# Dual_Supply_AC-DC.net
KiCad netlist of a schematic drawn in EAGLE
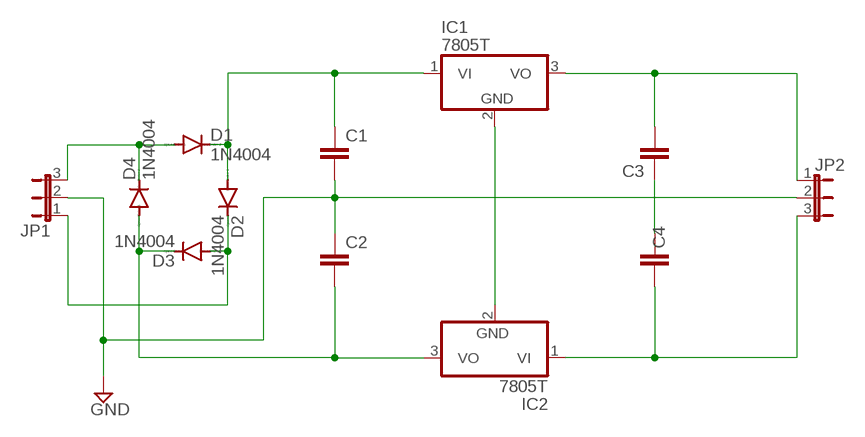
[diagram p0: schematic, sheet 1]

(export (version "E")
  (design (tool "Eeschema 10.0.6"))
  (components
    (comp (ref "C1")
      (value "C2,5-3")
      (footprint "eagle-import:C2.5-3")
      (libsource (lib "eagle-import") (part "C2,5-3"))
    )
    (comp (ref "C2")
      (value "C2,5-3")
      (footprint "eagle-import:C2.5-3")
      (libsource (lib "eagle-import") (part "C2,5-3"))
    )
    (comp (ref "C3")
      (value "C2,5-3")
      (footprint "eagle-import:C2.5-3")
      (libsource (lib "eagle-import") (part "C2,5-3"))
    )
    (comp (ref "C4")
      (value "C2,5-3")
      (footprint "eagle-import:C2.5-3")
      (libsource (lib "eagle-import") (part "C2,5-3"))
    )
    (comp (ref "D1")
      (value "1N4004")
      (footprint "eagle-import:DO41-10")
      (libsource (lib "eagle-import") (part "1N4004"))
    )
    (comp (ref "D2")
      (value "1N4004")
      (footprint "eagle-import:DO41-10")
      (libsource (lib "eagle-import") (part "1N4004"))
    )
    (comp (ref "D3")
      (value "1N4004")
      (footprint "eagle-import:DO41-10")
      (libsource (lib "eagle-import") (part "1N4004"))
    )
    (comp (ref "D4")
      (value "1N4004")
      (footprint "eagle-import:DO41-10")
      (libsource (lib "eagle-import") (part "1N4004"))
    )
    (comp (ref "IC1")
      (value "7805T")
      (footprint "eagle-import:TO220H")
      (libsource (lib "eagle-import") (part "78T05"))
    )
    (comp (ref "IC2")
      (value "7805T")
      (footprint "eagle-import:TO220H")
      (libsource (lib "eagle-import") (part "78T05"))
    )
    (comp (ref "JP1")
      (value "JP2E")
      (footprint "eagle-import:JP2")
      (libsource (lib "eagle-import") (part "JP2E"))
    )
    (comp (ref "JP2")
      (value "JP2E")
      (footprint "eagle-import:JP2")
      (libsource (lib "eagle-import") (part "JP2E"))
    )
  )
  (nets
    (net (code "1") (name "GND") (class "Default")
      (node (ref "C1") (pin "2") (pinfunction "2_2") (pintype "passive"))
      (node (ref "C2") (pin "1") (pinfunction "1_1") (pintype "passive"))
      (node (ref "JP1") (pin "2") (pinfunction "2_2") (pintype "passive"))
      (node (ref "JP2") (pin "2") (pinfunction "2_2") (pintype "passive"))
    )
    (net (code "2") (name "Net-(C3-Pad1)") (class "Default")
      (node (ref "C3") (pin "1") (pinfunction "1_1") (pintype "passive"))
      (node (ref "C4") (pin "1") (pinfunction "1_1") (pintype "passive"))
    )
    (net (code "3") (name "Net-(D1-PadA)") (class "Default")
      (node (ref "D1") (pin "A") (pinfunction "A_A") (pintype "passive"))
      (node (ref "D4") (pin "C") (pinfunction "C_C") (pintype "passive"))
      (node (ref "JP1") (pin "3") (pinfunction "3_3") (pintype "passive"))
    )
    (net (code "4") (name "Net-(D2-PadC)") (class "Default")
      (node (ref "D2") (pin "C") (pinfunction "C_C") (pintype "passive"))
      (node (ref "D3") (pin "A") (pinfunction "A_A") (pintype "passive"))
      (node (ref "JP1") (pin "1") (pinfunction "1_1") (pintype "passive"))
    )
    (net (code "5") (name "Net-(IC1-GND)") (class "Default")
      (node (ref "IC1") (pin "2") (pinfunction "GND_2") (pintype "passive"))
      (node (ref "IC2") (pin "2") (pinfunction "GND_2") (pintype "passive"))
    )
    (net (code "6") (name "Net-(IC1-VI)") (class "Default")
      (node (ref "C1") (pin "1") (pinfunction "1_1") (pintype "passive"))
      (node (ref "D1") (pin "C") (pinfunction "C_C") (pintype "passive"))
      (node (ref "D2") (pin "A") (pinfunction "A_A") (pintype "passive"))
      (node (ref "IC1") (pin "1") (pinfunction "VI_1") (pintype "input"))
    )
    (net (code "7") (name "Net-(IC1-VO)") (class "Default")
      (node (ref "C3") (pin "2") (pinfunction "2_2") (pintype "passive"))
      (node (ref "IC1") (pin "3") (pinfunction "VO_3") (pintype "passive"))
      (node (ref "JP2") (pin "1") (pinfunction "1_1") (pintype "passive"))
    )
    (net (code "8") (name "Net-(IC2-VI)") (class "Default")
      (node (ref "C4") (pin "2") (pinfunction "2_2") (pintype "passive"))
      (node (ref "IC2") (pin "1") (pinfunction "VI_1") (pintype "input"))
      (node (ref "JP2") (pin "3") (pinfunction "3_3") (pintype "passive"))
    )
    (net (code "9") (name "Net-(IC2-VO)") (class "Default")
      (node (ref "C2") (pin "2") (pinfunction "2_2") (pintype "passive"))
      (node (ref "D3") (pin "C") (pinfunction "C_C") (pintype "passive"))
      (node (ref "D4") (pin "A") (pinfunction "A_A") (pintype "passive"))
      (node (ref "IC2") (pin "3") (pinfunction "VO_3") (pintype "passive"))
    )
  )
)
